# Front.net
KiCad netlist of a schematic drawn in Altium Designer
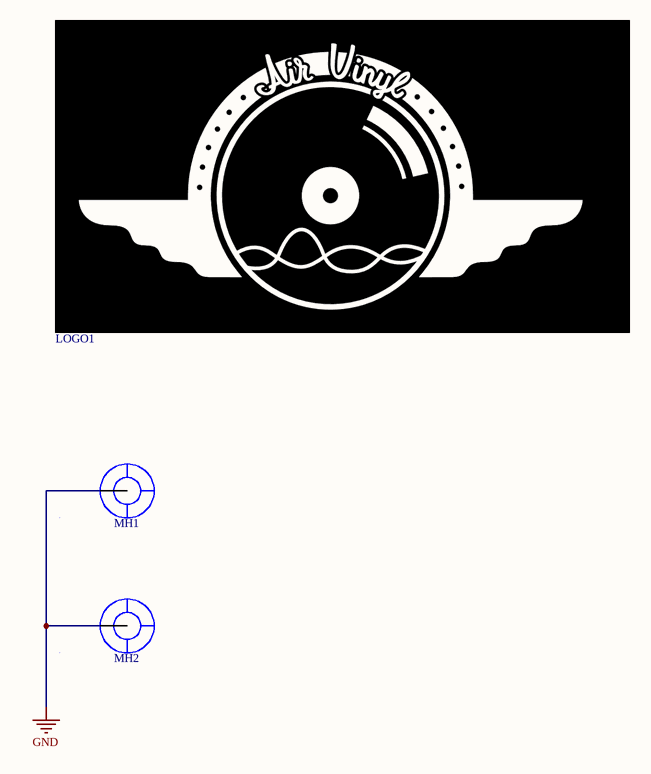
[diagram p0: Front.SchDoc]

(export (version "E")
  (design (tool "Eeschema 10.0.6"))
  (components
    (comp (ref "LOGO1")
      (value "Air Vinyl")
      (footprint "LOGO-AIR-Vinyl")
      (description "LOGO AIR Vinyl")
      (libsource (lib "micun") (part "LOGO-AirVinyl"))
    )
    (comp (ref "MH1")
      (value "Mounting hole")
      (footprint "MECH_MHOLE_3.5-GND-2")
      (libsource (lib "micun") (part "MECH_MHOLE_NET"))
    )
    (comp (ref "MH2")
      (value "Mounting hole")
      (footprint "MECH_MHOLE_3.5-GND-2")
      (libsource (lib "micun") (part "MECH_MHOLE_NET"))
    )
  )
  (nets
    (net (code "1") (name "GND") (class "Default")
      (node (ref "MH1") (pin "1") (pinfunction "NET_1") (pintype "power_in"))
      (node (ref "MH2") (pin "1") (pinfunction "NET_1") (pintype "power_in"))
    )
  )
)
